# Sheet1.net
KiCad netlist of a schematic drawn in Altium Designer
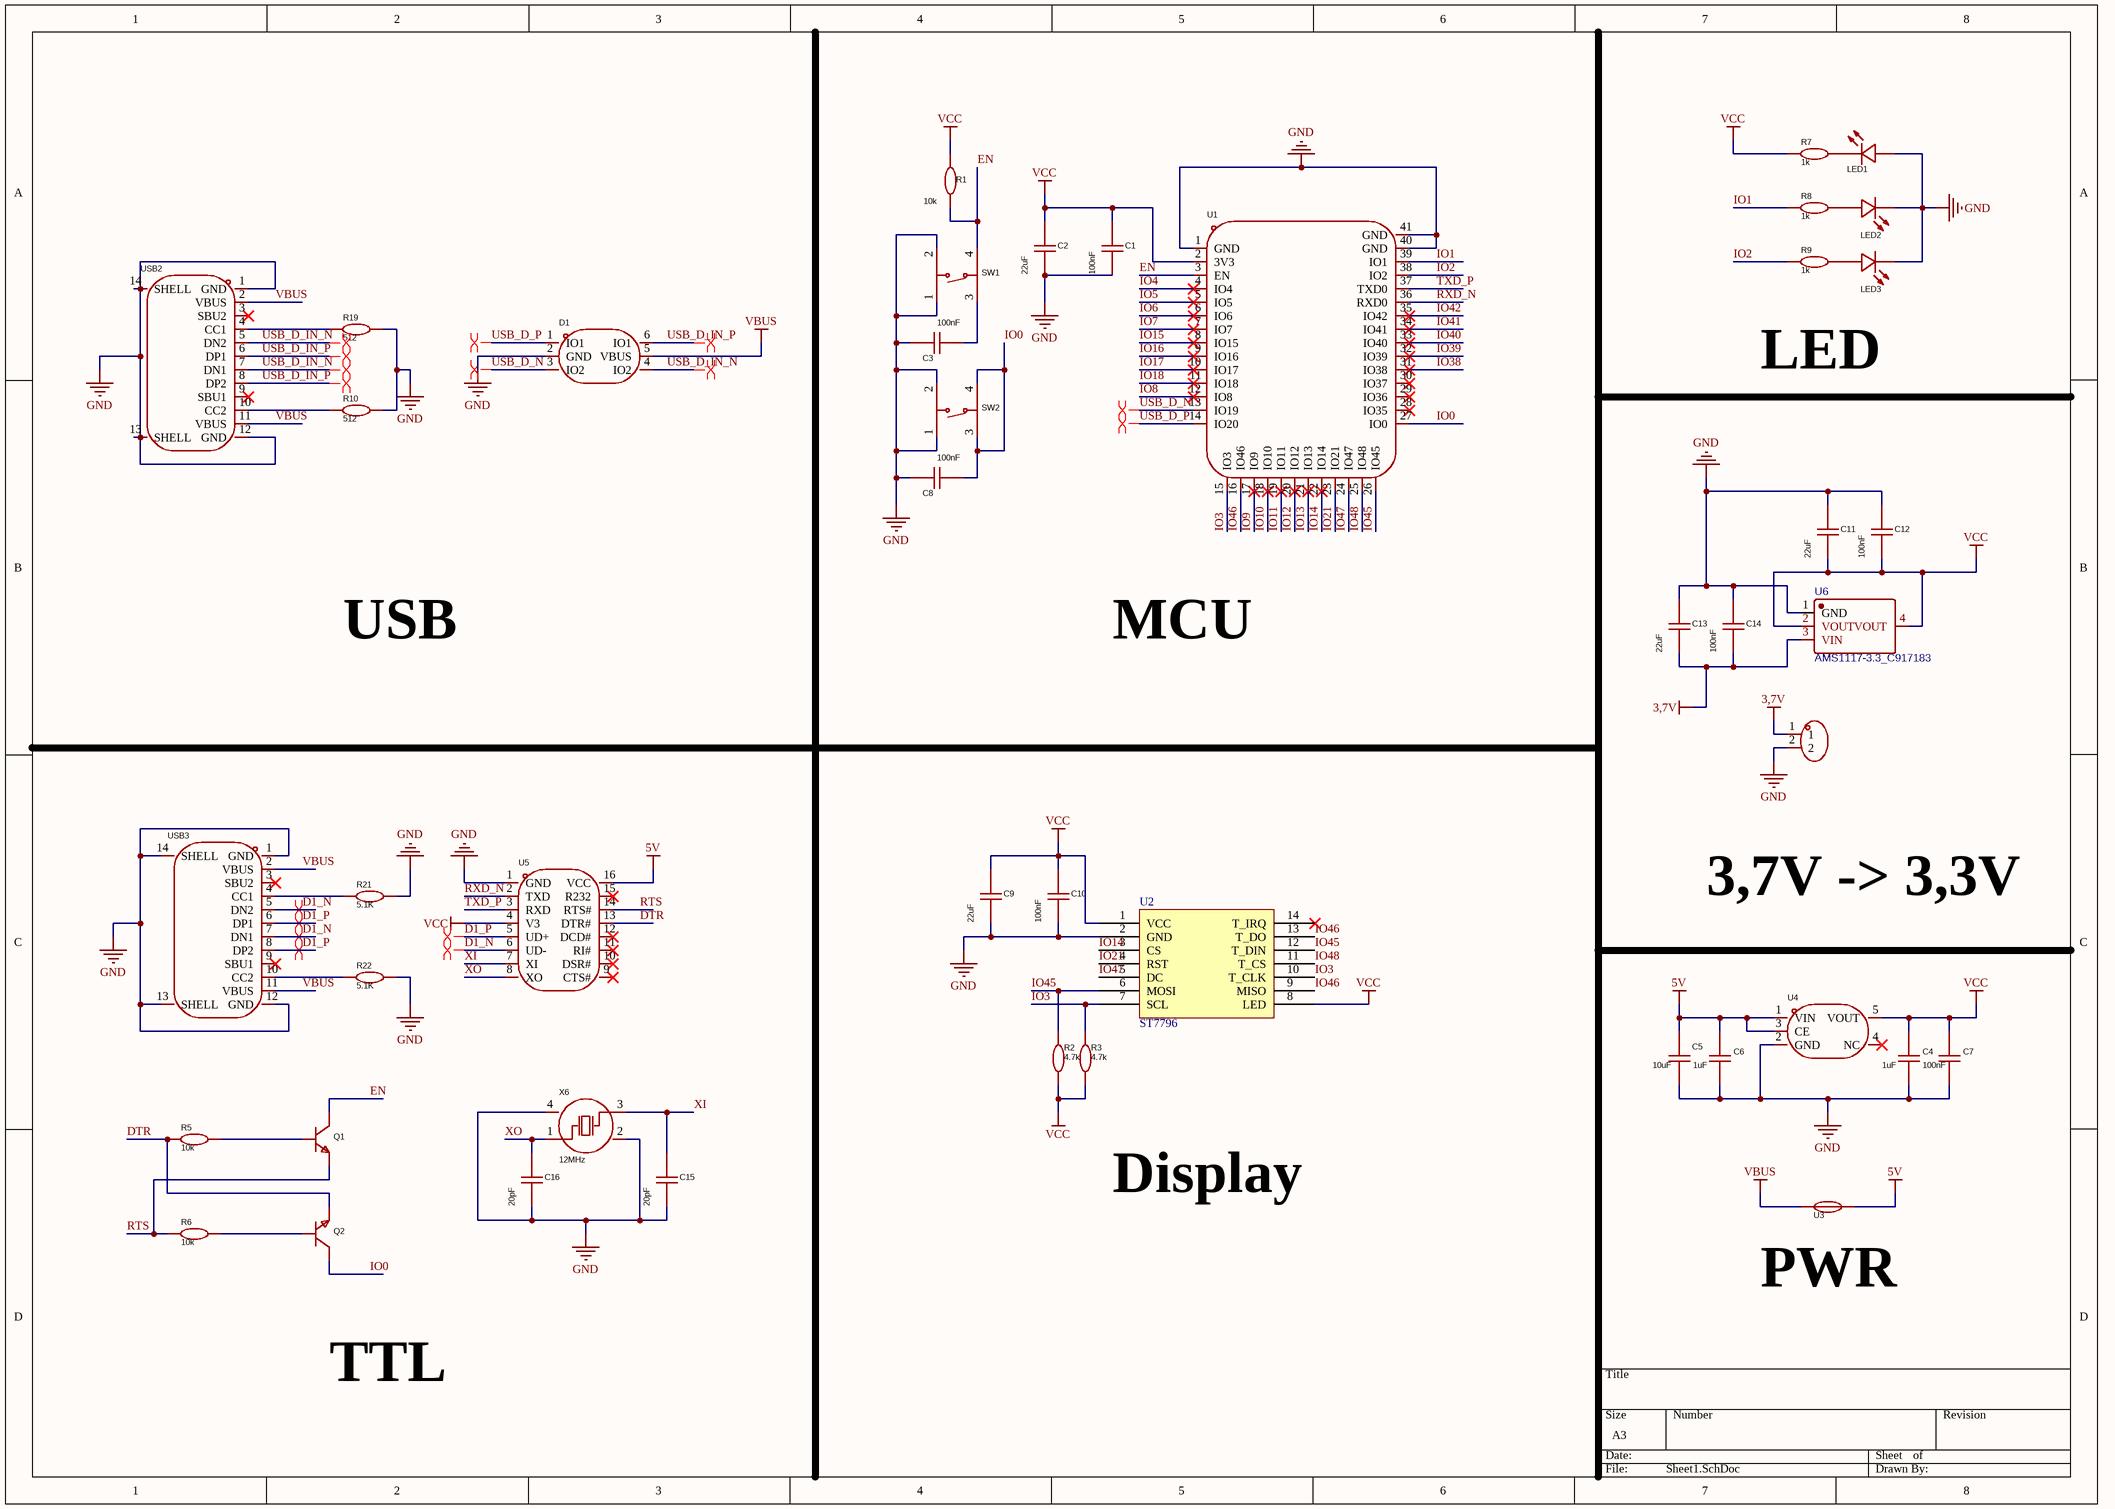
[diagram p0: Sheet1.SchDoc]

(export (version "E")
  (design (tool "Eeschema 10.0.6"))
  (components
    (comp (ref "C1")
      (value "100nF")
      (footprint "C0402")
      (fields
        (field (name "MANUFACTURER") "YAGEO(国巨)")
        (field (name "MANUFACTURER PART") "CC0603KRX7R9BB104")
        (field (name "TOLERANCE") "±10%")
      )
      (libsource (lib "Cap") (part "100n_22u"))
    )
    (comp (ref "C2")
      (value "22uF")
      (footprint "C0402")
      (fields
        (field (name "MANUFACTURER") "YAGEO(国巨)")
        (field (name "MANUFACTURER PART") "CC0603KRX7R9BB104")
        (field (name "TOLERANCE") "±10%")
      )
      (libsource (lib "Cap") (part "100n_22u"))
    )
    (comp (ref "C3")
      (value "100nF")
      (footprint "C0402")
      (fields
        (field (name "MANUFACTURER") "YAGEO(国巨)")
        (field (name "MANUFACTURER PART") "CC0603KRX7R9BB104")
        (field (name "TOLERANCE") "±10%")
      )
      (libsource (lib "Cap") (part "100n_22u"))
    )
    (comp (ref "C4")
      (value "1uF")
      (footprint "C0402")
      (fields
        (field (name "MANUFACTURER") "YAGEO(国巨)")
        (field (name "MANUFACTURER PART") "CC0603KRX7R9BB104")
        (field (name "TOLERANCE") "±10%")
      )
      (libsource (lib "Cap") (part "100n_22u"))
    )
    (comp (ref "C5")
      (value "10uF")
      (footprint "C0402")
      (fields
        (field (name "MANUFACTURER") "YAGEO(国巨)")
        (field (name "MANUFACTURER PART") "CC0603KRX7R9BB104")
        (field (name "TOLERANCE") "±10%")
      )
      (libsource (lib "Cap") (part "100n_22u"))
    )
    (comp (ref "C6")
      (value "1uF")
      (footprint "C0402")
      (fields
        (field (name "MANUFACTURER") "YAGEO(国巨)")
        (field (name "MANUFACTURER PART") "CC0603KRX7R9BB104")
        (field (name "TOLERANCE") "±10%")
      )
      (libsource (lib "Cap") (part "100n_22u"))
    )
    (comp (ref "C7")
      (value "100nF")
      (footprint "C0402")
      (fields
        (field (name "MANUFACTURER") "YAGEO(国巨)")
        (field (name "MANUFACTURER PART") "CC0603KRX7R9BB104")
        (field (name "TOLERANCE") "±10%")
      )
      (libsource (lib "Cap") (part "100n_22u"))
    )
    (comp (ref "C8")
      (value "100nF")
      (footprint "C0402")
      (fields
        (field (name "MANUFACTURER") "YAGEO(国巨)")
        (field (name "MANUFACTURER PART") "CC0603KRX7R9BB104")
        (field (name "TOLERANCE") "±10%")
      )
      (libsource (lib "Cap") (part "100n_22u"))
    )
    (comp (ref "C9")
      (value "22uF")
      (footprint "C0402")
      (fields
        (field (name "MANUFACTURER") "YAGEO(国巨)")
        (field (name "MANUFACTURER PART") "CC0603KRX7R9BB104")
        (field (name "TOLERANCE") "±10%")
      )
      (libsource (lib "Cap") (part "100n_22u"))
    )
    (comp (ref "C10")
      (value "100nF")
      (footprint "C0402")
      (fields
        (field (name "MANUFACTURER") "YAGEO(国巨)")
        (field (name "MANUFACTURER PART") "CC0603KRX7R9BB104")
        (field (name "TOLERANCE") "±10%")
      )
      (libsource (lib "Cap") (part "100n_22u"))
    )
    (comp (ref "C11")
      (value "22uF")
      (footprint "C0402")
      (fields
        (field (name "MANUFACTURER") "YAGEO(国巨)")
        (field (name "MANUFACTURER PART") "CC0603KRX7R9BB104")
        (field (name "TOLERANCE") "±10%")
      )
      (libsource (lib "Cap") (part "100n_22u"))
    )
    (comp (ref "C12")
      (value "100nF")
      (footprint "C0402")
      (fields
        (field (name "MANUFACTURER") "YAGEO(国巨)")
        (field (name "MANUFACTURER PART") "CC0603KRX7R9BB104")
        (field (name "TOLERANCE") "±10%")
      )
      (libsource (lib "Cap") (part "100n_22u"))
    )
    (comp (ref "C13")
      (value "22uF")
      (footprint "C0402")
      (fields
        (field (name "MANUFACTURER") "YAGEO(国巨)")
        (field (name "MANUFACTURER PART") "CC0603KRX7R9BB104")
        (field (name "TOLERANCE") "±10%")
      )
      (libsource (lib "Cap") (part "100n_22u"))
    )
    (comp (ref "C14")
      (value "100nF")
      (footprint "C0402")
      (fields
        (field (name "MANUFACTURER") "YAGEO(国巨)")
        (field (name "MANUFACTURER PART") "CC0603KRX7R9BB104")
        (field (name "TOLERANCE") "±10%")
      )
      (libsource (lib "Cap") (part "100n_22u"))
    )
    (comp (ref "C15")
      (value "20pF")
      (footprint "C0402")
      (fields
        (field (name "MANUFACTURER") "YAGEO(国巨)")
        (field (name "MANUFACTURER PART") "CC0603KRX7R9BB104")
        (field (name "TOLERANCE") "±10%")
      )
      (libsource (lib "Cap") (part "100n_22u"))
    )
    (comp (ref "C16")
      (value "20pF")
      (footprint "C0402")
      (fields
        (field (name "MANUFACTURER") "YAGEO(国巨)")
        (field (name "MANUFACTURER PART") "CC0603KRX7R9BB104")
        (field (name "TOLERANCE") "±10%")
      )
      (libsource (lib "Cap") (part "100n_22u"))
    )
    (comp (ref "D1")
      (value "USBLC6-2SC6")
      (footprint "SOT-23-6_L2.9-W1.6-P0.95-LS2.8-BL")
      (fields (field (name "MANUFACTURER") "TECH PUBLIC(台舟)"))
      (libsource (lib "USBLC6-2SC6_C28276541_") (part "USBLC6-2SC6_C2827654"))
    )
    (comp (ref "LED1")
      (value "MHT192WDT-CYAN")
      (footprint "LED0603-Yel")
      (fields (field (name "MANUFACTURER") "MEIHUA(美华)"))
      (libsource (lib "Led") (part "LED"))
    )
    (comp (ref "LED2")
      (value "MHT192WDT-CYAN")
      (footprint "LED0603-R-RD_BLUE")
      (fields (field (name "MANUFACTURER") "MEIHUA(美华)"))
      (libsource (lib "Led") (part "LED"))
    )
    (comp (ref "LED3")
      (value "MHT192WDT-CYAN")
      (footprint "LED0603-R-RD_BLUE")
      (fields (field (name "MANUFACTURER") "MEIHUA(美华)"))
      (libsource (lib "Led") (part "LED"))
    )
    (comp (ref "Q1")
      (value "S8050")
      (footprint "SOT-23-3_L2.9-W1.3-P1.90-LS2.4-BR")
      (fields (field (name "MANUFACTURER") "YONGYUTAI(永裕泰)"))
      (libsource (lib "S8050_C28918041") (part "S8050_C2891804"))
    )
    (comp (ref "Q2")
      (value "S8050")
      (footprint "SOT-23-3_L2.9-W1.3-P1.90-LS2.4-BR")
      (fields (field (name "MANUFACTURER") "YONGYUTAI(永裕泰)"))
      (libsource (lib "S8050_C28918041") (part "S8050_C2891804"))
    )
    (comp (ref "R1")
      (value "10k")
      (footprint "R0402")
      (fields
        (field (name "MANUFACTURER") "YAGEO(国巨)")
        (field (name "MANUFACTURER PART") "RC0402FR-0710KL")
        (field (name "TOLERANCE") "±1%")
      )
      (libsource (lib "Res") (part "10k"))
    )
    (comp (ref "R2")
      (value "4.7k")
      (footprint "R0402")
      (fields
        (field (name "MANUFACTURER") "YAGEO(国巨)")
        (field (name "MANUFACTURER PART") "RC0402FR-0710KL")
        (field (name "TOLERANCE") "±1%")
      )
      (libsource (lib "Res") (part "10k"))
    )
    (comp (ref "R3")
      (value "4.7k")
      (footprint "R0402")
      (fields
        (field (name "MANUFACTURER") "YAGEO(国巨)")
        (field (name "MANUFACTURER PART") "RC0402FR-0710KL")
        (field (name "TOLERANCE") "±1%")
      )
      (libsource (lib "Res") (part "10k"))
    )
    (comp (ref "R5")
      (value "10k")
      (footprint "R0402")
      (fields
        (field (name "MANUFACTURER") "YAGEO(国巨)")
        (field (name "MANUFACTURER PART") "RC0402FR-0710KL")
        (field (name "TOLERANCE") "±1%")
      )
      (libsource (lib "Res") (part "10k"))
    )
    (comp (ref "R6")
      (value "10k")
      (footprint "R0402")
      (fields
        (field (name "MANUFACTURER") "YAGEO(国巨)")
        (field (name "MANUFACTURER PART") "RC0402FR-0710KL")
        (field (name "TOLERANCE") "±1%")
      )
      (libsource (lib "Res") (part "10k"))
    )
    (comp (ref "R7")
      (value "1k")
      (footprint "R0402")
      (fields
        (field (name "MANUFACTURER") "YAGEO(国巨)")
        (field (name "MANUFACTURER PART") "RC0402FR-0710KL")
        (field (name "TOLERANCE") "±1%")
      )
      (libsource (lib "Res") (part "10k"))
    )
    (comp (ref "R8")
      (value "1k")
      (footprint "R0402")
      (fields
        (field (name "MANUFACTURER") "YAGEO(国巨)")
        (field (name "MANUFACTURER PART") "RC0402FR-0710KL")
        (field (name "TOLERANCE") "±1%")
      )
      (libsource (lib "Res") (part "10k"))
    )
    (comp (ref "R9")
      (value "1k")
      (footprint "R0402")
      (fields
        (field (name "MANUFACTURER") "YAGEO(国巨)")
        (field (name "MANUFACTURER PART") "RC0402FR-0710KL")
        (field (name "TOLERANCE") "±1%")
      )
      (libsource (lib "Res") (part "10k"))
    )
    (comp (ref "R10")
      (value "512")
      (footprint "R0402")
      (fields
        (field (name "MANUFACTURER") "YAGEO(国巨)")
        (field (name "MANUFACTURER PART") "RC0402FR-0710KL")
        (field (name "TOLERANCE") "±1%")
      )
      (libsource (lib "Res") (part "10k"))
    )
    (comp (ref "R19")
      (value "512")
      (footprint "R0402")
      (fields
        (field (name "MANUFACTURER") "YAGEO(国巨)")
        (field (name "MANUFACTURER PART") "RC0402FR-0710KL")
        (field (name "TOLERANCE") "±1%")
      )
      (libsource (lib "Res") (part "10k"))
    )
    (comp (ref "R21")
      (value "5.1K")
      (footprint "R0402")
      (fields
        (field (name "MANUFACTURER") "YAGEO(国巨)")
        (field (name "MANUFACTURER PART") "RC0402FR-0710KL")
        (field (name "TOLERANCE") "±1%")
      )
      (libsource (lib "Res") (part "10k"))
    )
    (comp (ref "R22")
      (value "5.1K")
      (footprint "R0402")
      (fields
        (field (name "MANUFACTURER") "YAGEO(国巨)")
        (field (name "MANUFACTURER PART") "RC0402FR-0710KL")
        (field (name "TOLERANCE") "±1%")
      )
      (libsource (lib "Res") (part "10k"))
    )
    (comp (ref "SW1")
      (value "TS-1089S-02526")
      (footprint "SW-SMD_4P-L4.2-W3.3-P2.15-LS5.1")
      (fields (field (name "MANUFACTURER") "XUNPU(讯普)"))
      (libsource (lib "TS-1089S-025261_TS-1089S-02526") (part "TS-1089S-02526"))
    )
    (comp (ref "SW2")
      (value "TS-1089S-02526")
      (footprint "SW-SMD_4P-L4.2-W3.3-P2.15-LS5.1")
      (fields (field (name "MANUFACTURER") "XUNPU(讯普)"))
      (libsource (lib "TS-1089S-025261_TS-1089S-02526") (part "TS-1089S-02526"))
    )
    (comp (ref "U1")
      (value "ESP32-S3-WROOM-1-N16R2")
      (footprint "WIRELM-SMD_ESP32-S3-WROOM-1")
      (fields (field (name "MANUFACTURER") "ESPRESSIF(乐鑫)"))
      (libsource (lib "ESP32-S3-WROOM-1(N16R2)") (part "ESP32-S3-WROOM-1-N16R2"))
    )
    (comp (ref "U2") (value "ST7796") (footprint "ST7796") (libsource (lib "Schlib1") (part "ST7796")))
    (comp (ref "U3")
      (value "SMD0805B050TF")
      (footprint "F0805")
      (fields (field (name "MANUFACTURER") "Brightking(君耀电子)"))
      (libsource (lib "SMD0805B050TF") (part "SMD0805B050TF"))
    )
    (comp (ref "U4")
      (value "RT9013-33GB-JSM")
      (footprint "SOT-23-5_L2.9-W1.6-P0.95-LS2.8-BR")
      (fields (field (name "MANUFACTURER") "JSMSEMI(杰盛微)"))
      (libsource (lib "RT9013-33GB") (part "RT9013-33GB-JSM"))
    )
    (comp (ref "U5")
      (value "CH340G")
      (footprint "SOIC-16_L9.9-W3.9-P1.27-LS6.0-BL")
      (fields (field (name "MANUFACTURER") "WCH(南京沁恒)"))
      (libsource (lib "CH340G") (part "CH340G"))
    )
    (comp (ref "U6")
      (value "AMS1117-3.3_C917183")
      (footprint "SOT-223-3_L6.7-W3.7-P2.30-LS7.0-BR")
      (fields
        (field (name "MANUFACTURER") "JSMSEMI(杰盛微)")
        (field (name "MANUFACTURER PART") "AMS1117-3.3")
        (field (name "CONTRIBUTOR") "LCSC")
      )
      (libsource (lib "AMS1117-3.3") (part "AMS1117-3.3_C917183"))
    )
    (comp (ref "U7")
      (value "WAFER-XH254Z-2A")
      (footprint "CONN-TH_2P-P2.50_XH-2A_3045048")
      (fields (field (name "MANUFACTURER") "HANBO(汉博)"))
      (libsource (lib "WAFER-XH254Z-2A") (part "WAFER-XH254Z-2A"))
    )
    (comp (ref "USB2")
      (value "TYPE-C 16PIN 2MD(073)")
      (footprint "USB-C-SMD_TYPE-C-6PIN-2MD-073")
      (fields (field (name "MANUFACTURER") "SHOU HAN(首韩)"))
      (libsource (lib "TYPE-C 16PIN 2MD(073)") (part "TYPE-C 16PIN 2MD(073)"))
    )
    (comp (ref "USB3")
      (value "TYPE-C 16PIN 2MD(073)")
      (footprint "USB-C-SMD_TYPE-C-6PIN-2MD-073")
      (fields (field (name "MANUFACTURER") "SHOU HAN(首韩)"))
      (libsource (lib "TYPE-C 16PIN 2MD(073)") (part "TYPE-C 16PIN 2MD(073)"))
    )
    (comp (ref "X6")
      (value "12MHz")
      (footprint "CRYSTAL-SMD_4P-L3.2-W2.5-BL")
      (fields (field (name "MANUFACTURER") "YXC(扬兴晶振)") (field (name "MANUFACTURER PART") "X322512MSB4SI"))
      (libsource (lib "X322512MSB4SI") (part "X322512MSB4SI"))
    )
  )
  (nets
    (net (code "1") (name "/D1_N") (class "Default")
      (node (ref "U5") (pin "6") (pinfunction "UD-_6") (pintype "passive"))
      (node (ref "USB3") (pin "5") (pinfunction "DN2_5") (pintype "passive"))
      (node (ref "USB3") (pin "7") (pinfunction "DN1_7") (pintype "passive"))
    )
    (net (code "2") (name "/D1_P") (class "Default")
      (node (ref "U5") (pin "5") (pinfunction "UD+_5") (pintype "passive"))
      (node (ref "USB3") (pin "6") (pinfunction "DP1_6") (pintype "passive"))
      (node (ref "USB3") (pin "8") (pinfunction "DP2_8") (pintype "passive"))
    )
    (net (code "3") (name "/DTR") (class "Default")
      (node (ref "Q2") (pin "2") (pinfunction "E_2") (pintype "passive"))
      (node (ref "R5") (pin "2") (pinfunction "2_2") (pintype "passive"))
      (node (ref "U5") (pin "13") (pinfunction "DTR#_13") (pintype "passive"))
    )
    (net (code "4") (name "/EN") (class "Default")
      (node (ref "Q1") (pin "3") (pinfunction "C_3") (pintype "passive"))
      (node (ref "R1") (pin "1") (pinfunction "1_1") (pintype "passive"))
      (node (ref "SW1") (pin "4") (pinfunction "4_4") (pintype "passive"))
      (node (ref "U1") (pin "3") (pinfunction "EN_3") (pintype "passive"))
    )
    (net (code "5") (name "/IO0") (class "Default")
      (node (ref "C8") (pin "1") (pinfunction "1_1") (pintype "passive"))
      (node (ref "Q2") (pin "3") (pinfunction "C_3") (pintype "passive"))
      (node (ref "SW2") (pin "3") (pinfunction "3_3") (pintype "passive"))
      (node (ref "SW2") (pin "4") (pinfunction "4_4") (pintype "passive"))
      (node (ref "U1") (pin "27") (pinfunction "IO0_27") (pintype "passive"))
    )
    (net (code "6") (name "/IO1") (class "Default")
      (node (ref "R8") (pin "2") (pinfunction "2_2") (pintype "passive"))
      (node (ref "U1") (pin "39") (pinfunction "IO1_39") (pintype "passive"))
    )
    (net (code "7") (name "/IO2") (class "Default")
      (node (ref "R9") (pin "2") (pinfunction "2_2") (pintype "passive"))
      (node (ref "U1") (pin "38") (pinfunction "IO2_38") (pintype "passive"))
    )
    (net (code "8") (name "/IO3") (class "Default")
      (node (ref "R3") (pin "1") (pinfunction "1_1") (pintype "passive"))
      (node (ref "U1") (pin "15") (pinfunction "IO3_15") (pintype "passive"))
      (node (ref "U2") (pin "10") (pinfunction "T_CLK_10") (pintype "passive"))
      (node (ref "U2") (pin "7") (pinfunction "SCL_7") (pintype "passive"))
    )
    (net (code "9") (name "/IO4") (class "Default")
      (node (ref "U1") (pin "4") (pinfunction "IO4_4") (pintype "passive+no_connect"))
    )
    (net (code "10") (name "/IO5") (class "Default")
      (node (ref "U1") (pin "5") (pinfunction "IO5_5") (pintype "passive+no_connect"))
    )
    (net (code "11") (name "/IO6") (class "Default")
      (node (ref "U1") (pin "6") (pinfunction "IO6_6") (pintype "passive+no_connect"))
    )
    (net (code "12") (name "/IO7") (class "Default")
      (node (ref "U1") (pin "7") (pinfunction "IO7_7") (pintype "passive+no_connect"))
    )
    (net (code "13") (name "/IO8") (class "Default")
      (node (ref "U1") (pin "12") (pinfunction "IO8_12") (pintype "passive+no_connect"))
    )
    (net (code "14") (name "/IO9") (class "Default")
      (node (ref "U1") (pin "17") (pinfunction "IO9_17") (pintype "passive+no_connect"))
    )
    (net (code "15") (name "/IO10") (class "Default")
      (node (ref "U1") (pin "18") (pinfunction "IO10_18") (pintype "passive+no_connect"))
    )
    (net (code "16") (name "/IO11") (class "Default")
      (node (ref "U1") (pin "19") (pinfunction "IO11_19") (pintype "passive+no_connect"))
    )
    (net (code "17") (name "/IO12") (class "Default")
      (node (ref "U1") (pin "20") (pinfunction "IO12_20") (pintype "passive+no_connect"))
    )
    (net (code "18") (name "/IO13") (class "Default")
      (node (ref "U1") (pin "21") (pinfunction "IO13_21") (pintype "passive+no_connect"))
    )
    (net (code "19") (name "/IO14") (class "Default")
      (node (ref "U1") (pin "22") (pinfunction "IO14_22") (pintype "passive"))
      (node (ref "U2") (pin "3") (pinfunction "CS_3") (pintype "passive"))
    )
    (net (code "20") (name "/IO15") (class "Default")
      (node (ref "U1") (pin "8") (pinfunction "IO15_8") (pintype "passive+no_connect"))
    )
    (net (code "21") (name "/IO16") (class "Default")
      (node (ref "U1") (pin "9") (pinfunction "IO16_9") (pintype "passive+no_connect"))
    )
    (net (code "22") (name "/IO17") (class "Default")
      (node (ref "U1") (pin "10") (pinfunction "IO17_10") (pintype "passive+no_connect"))
    )
    (net (code "23") (name "/IO18") (class "Default")
      (node (ref "U1") (pin "11") (pinfunction "IO18_11") (pintype "passive+no_connect"))
    )
    (net (code "24") (name "/IO21") (class "Default")
      (node (ref "U1") (pin "23") (pinfunction "IO21_23") (pintype "passive"))
      (node (ref "U2") (pin "4") (pinfunction "RST_4") (pintype "passive"))
    )
    (net (code "25") (name "/IO38") (class "Default")
      (node (ref "U1") (pin "31") (pinfunction "IO38_31") (pintype "passive+no_connect"))
    )
    (net (code "26") (name "/IO39") (class "Default")
      (node (ref "U1") (pin "32") (pinfunction "IO39_32") (pintype "passive+no_connect"))
    )
    (net (code "27") (name "/IO40") (class "Default")
      (node (ref "U1") (pin "33") (pinfunction "IO40_33") (pintype "passive+no_connect"))
    )
    (net (code "28") (name "/IO41") (class "Default")
      (node (ref "U1") (pin "34") (pinfunction "IO41_34") (pintype "passive+no_connect"))
    )
    (net (code "29") (name "/IO42") (class "Default")
      (node (ref "U1") (pin "35") (pinfunction "IO42_35") (pintype "passive+no_connect"))
    )
    (net (code "30") (name "/IO45") (class "Default")
      (node (ref "R2") (pin "1") (pinfunction "1_1") (pintype "passive"))
      (node (ref "U1") (pin "26") (pinfunction "IO45_26") (pintype "passive"))
      (node (ref "U2") (pin "12") (pinfunction "T_DIN_12") (pintype "passive"))
      (node (ref "U2") (pin "6") (pinfunction "MOSI_6") (pintype "passive"))
    )
    (net (code "31") (name "/IO46") (class "Default")
      (node (ref "U1") (pin "16") (pinfunction "IO46_16") (pintype "passive"))
      (node (ref "U2") (pin "13") (pinfunction "T_DO_13") (pintype "passive"))
      (node (ref "U2") (pin "9") (pinfunction "MISO_9") (pintype "passive"))
    )
    (net (code "32") (name "/IO47") (class "Default")
      (node (ref "U1") (pin "24") (pinfunction "IO47_24") (pintype "passive"))
      (node (ref "U2") (pin "5") (pinfunction "DC_5") (pintype "passive"))
    )
    (net (code "33") (name "/IO48") (class "Default")
      (node (ref "U1") (pin "25") (pinfunction "IO48_25") (pintype "passive"))
      (node (ref "U2") (pin "11") (pinfunction "T_CS_11") (pintype "passive"))
    )
    (net (code "34") (name "/RTS") (class "Default")
      (node (ref "Q1") (pin "2") (pinfunction "E_2") (pintype "passive"))
      (node (ref "R6") (pin "2") (pinfunction "2_2") (pintype "passive"))
      (node (ref "U5") (pin "14") (pinfunction "RTS#_14") (pintype "passive"))
    )
    (net (code "35") (name "/RXD_N") (class "Default")
      (node (ref "U1") (pin "36") (pinfunction "RXD0_36") (pintype "passive"))
      (node (ref "U5") (pin "2") (pinfunction "TXD_2") (pintype "passive"))
    )
    (net (code "36") (name "/TXD_P") (class "Default")
      (node (ref "U1") (pin "37") (pinfunction "TXD0_37") (pintype "passive"))
      (node (ref "U5") (pin "3") (pinfunction "RXD_3") (pintype "passive"))
    )
    (net (code "37") (name "/USB_D_IN_N") (class "Default")
      (node (ref "D1") (pin "4") (pinfunction "IO2_4") (pintype "passive"))
      (node (ref "USB2") (pin "5") (pinfunction "DN2_5") (pintype "passive"))
      (node (ref "USB2") (pin "7") (pinfunction "DN1_7") (pintype "passive"))
    )
    (net (code "38") (name "/USB_D_IN_P") (class "Default")
      (node (ref "D1") (pin "6") (pinfunction "IO1_6") (pintype "passive"))
      (node (ref "USB2") (pin "6") (pinfunction "DP1_6") (pintype "passive"))
      (node (ref "USB2") (pin "8") (pinfunction "DP2_8") (pintype "passive"))
    )
    (net (code "39") (name "/USB_D_N") (class "Default")
      (node (ref "D1") (pin "3") (pinfunction "IO2_3") (pintype "passive"))
      (node (ref "U1") (pin "13") (pinfunction "IO19_13") (pintype "passive"))
    )
    (net (code "40") (name "/USB_D_P") (class "Default")
      (node (ref "D1") (pin "1") (pinfunction "IO1_1") (pintype "passive"))
      (node (ref "U1") (pin "14") (pinfunction "IO20_14") (pintype "passive"))
    )
    (net (code "41") (name "/XI") (class "Default")
      (node (ref "C15") (pin "2") (pinfunction "2_2") (pintype "passive"))
      (node (ref "U5") (pin "7") (pinfunction "XI_7") (pintype "passive"))
      (node (ref "X6") (pin "3") (pinfunction "OSC2_3") (pintype "passive"))
    )
    (net (code "42") (name "/XO") (class "Default")
      (node (ref "C16") (pin "2") (pinfunction "2_2") (pintype "passive"))
      (node (ref "U5") (pin "8") (pinfunction "XO_8") (pintype "passive"))
      (node (ref "X6") (pin "1") (pinfunction "OSC1_1") (pintype "passive"))
    )
    (net (code "43") (name "3,7V") (class "Default")
      (node (ref "C13") (pin "1") (pinfunction "1_1") (pintype "passive"))
      (node (ref "C14") (pin "1") (pinfunction "1_1") (pintype "passive"))
      (node (ref "U6") (pin "3") (pinfunction "VIN_3") (pintype "passive"))
      (node (ref "U7") (pin "1") (pinfunction "1_1") (pintype "passive"))
    )
    (net (code "44") (name "5V") (class "Default")
      (node (ref "C5") (pin "1") (pinfunction "1_1") (pintype "passive"))
      (node (ref "C6") (pin "2") (pinfunction "2_2") (pintype "passive"))
      (node (ref "U3") (pin "2") (pinfunction "2_2") (pintype "passive"))
      (node (ref "U4") (pin "1") (pinfunction "VIN_1") (pintype "passive"))
      (node (ref "U4") (pin "3") (pinfunction "CE_3") (pintype "passive"))
      (node (ref "U5") (pin "16") (pinfunction "VCC_16") (pintype "passive"))
    )
    (net (code "45") (name "GND") (class "Default")
      (node (ref "C1") (pin "1") (pinfunction "1_1") (pintype "passive"))
      (node (ref "C10") (pin "1") (pinfunction "1_1") (pintype "passive"))
      (node (ref "C11") (pin "2") (pinfunction "2_2") (pintype "passive"))
      (node (ref "C12") (pin "2") (pinfunction "2_2") (pintype "passive"))
      (node (ref "C13") (pin "2") (pinfunction "2_2") (pintype "passive"))
      (node (ref "C14") (pin "2") (pinfunction "2_2") (pintype "passive"))
      (node (ref "C15") (pin "1") (pinfunction "1_1") (pintype "passive"))
      (node (ref "C16") (pin "1") (pinfunction "1_1") (pintype "passive"))
      (node (ref "C2") (pin "1") (pinfunction "1_1") (pintype "passive"))
      (node (ref "C3") (pin "2") (pinfunction "2_2") (pintype "passive"))
      (node (ref "C4") (pin "1") (pinfunction "1_1") (pintype "passive"))
      (node (ref "C5") (pin "2") (pinfunction "2_2") (pintype "passive"))
      (node (ref "C6") (pin "1") (pinfunction "1_1") (pintype "passive"))
      (node (ref "C7") (pin "1") (pinfunction "1_1") (pintype "passive"))
      (node (ref "C8") (pin "2") (pinfunction "2_2") (pintype "passive"))
      (node (ref "C9") (pin "1") (pinfunction "1_1") (pintype "passive"))
      (node (ref "D1") (pin "2") (pinfunction "GND_2") (pintype "passive"))
      (node (ref "LED1") (pin "2") (pinfunction "K_2") (pintype "passive"))
      (node (ref "LED2") (pin "1") (pinfunction "A_1") (pintype "passive"))
      (node (ref "LED3") (pin "1") (pinfunction "A_1") (pintype "passive"))
      (node (ref "R10") (pin "1") (pinfunction "1_1") (pintype "passive"))
      (node (ref "R19") (pin "1") (pinfunction "1_1") (pintype "passive"))
      (node (ref "R21") (pin "1") (pinfunction "1_1") (pintype "passive"))
      (node (ref "R22") (pin "1") (pinfunction "1_1") (pintype "passive"))
      (node (ref "SW1") (pin "1") (pinfunction "1_1") (pintype "passive"))
      (node (ref "SW1") (pin "2") (pinfunction "2_2") (pintype "passive"))
      (node (ref "SW2") (pin "1") (pinfunction "1_1") (pintype "passive"))
      (node (ref "SW2") (pin "2") (pinfunction "2_2") (pintype "passive"))
      (node (ref "U1") (pin "1") (pinfunction "GND_1") (pintype "passive"))
      (node (ref "U1") (pin "40") (pinfunction "GND_40") (pintype "passive"))
      (node (ref "U1") (pin "41") (pinfunction "GND_41") (pintype "passive"))
      (node (ref "U2") (pin "2") (pinfunction "GND_2") (pintype "passive"))
      (node (ref "U4") (pin "2") (pinfunction "GND_2") (pintype "passive"))
      (node (ref "U5") (pin "1") (pinfunction "GND_1") (pintype "passive"))
      (node (ref "U6") (pin "1") (pinfunction "GND_1") (pintype "passive"))
      (node (ref "U7") (pin "2") (pinfunction "2_2") (pintype "passive"))
      (node (ref "USB2") (pin "1") (pinfunction "GND_1") (pintype "passive"))
      (node (ref "USB2") (pin "12") (pinfunction "GND_12") (pintype "passive"))
      (node (ref "USB2") (pin "13") (pinfunction "SHELL_13") (pintype "passive"))
      (node (ref "USB2") (pin "14") (pinfunction "SHELL_14") (pintype "passive"))
      (node (ref "USB3") (pin "1") (pinfunction "GND_1") (pintype "passive"))
      (node (ref "USB3") (pin "12") (pinfunction "GND_12") (pintype "passive"))
      (node (ref "USB3") (pin "13") (pinfunction "SHELL_13") (pintype "passive"))
      (node (ref "USB3") (pin "14") (pinfunction "SHELL_14") (pintype "passive"))
      (node (ref "X6") (pin "2") (pinfunction "GND_2") (pintype "passive"))
      (node (ref "X6") (pin "4") (pinfunction "GND_4") (pintype "passive"))
    )
    (net (code "46") (name "Net-(C3-Pad1)") (class "Default")
      (node (ref "C3") (pin "1") (pinfunction "1_1") (pintype "passive"))
      (node (ref "SW1") (pin "3") (pinfunction "3_3") (pintype "passive"))
    )
    (net (code "47") (name "Net-(LED1-A)") (class "Default")
      (node (ref "LED1") (pin "1") (pinfunction "A_1") (pintype "passive"))
      (node (ref "R7") (pin "1") (pinfunction "1_1") (pintype "passive"))
    )
    (net (code "48") (name "Net-(LED2-K)") (class "Default")
      (node (ref "LED2") (pin "2") (pinfunction "K_2") (pintype "passive"))
      (node (ref "R8") (pin "1") (pinfunction "1_1") (pintype "passive"))
    )
    (net (code "49") (name "Net-(LED3-K)") (class "Default")
      (node (ref "LED3") (pin "2") (pinfunction "K_2") (pintype "passive"))
      (node (ref "R9") (pin "1") (pinfunction "1_1") (pintype "passive"))
    )
    (net (code "50") (name "Net-(Q1-B)") (class "Default")
      (node (ref "Q1") (pin "1") (pinfunction "B_1") (pintype "passive"))
      (node (ref "R5") (pin "1") (pinfunction "1_1") (pintype "passive"))
    )
    (net (code "51") (name "Net-(Q2-B)") (class "Default")
      (node (ref "Q2") (pin "1") (pinfunction "B_1") (pintype "passive"))
      (node (ref "R6") (pin "1") (pinfunction "1_1") (pintype "passive"))
    )
    (net (code "52") (name "Net-(USB2-CC1)") (class "Default")
      (node (ref "R19") (pin "2") (pinfunction "2_2") (pintype "passive"))
      (node (ref "USB2") (pin "4") (pinfunction "CC1_4") (pintype "passive"))
    )
    (net (code "53") (name "Net-(USB2-CC2)") (class "Default")
      (node (ref "R10") (pin "2") (pinfunction "2_2") (pintype "passive"))
      (node (ref "USB2") (pin "10") (pinfunction "CC2_10") (pintype "passive"))
    )
    (net (code "54") (name "Net-(USB3-CC1)") (class "Default")
      (node (ref "R21") (pin "2") (pinfunction "2_2") (pintype "passive"))
      (node (ref "USB3") (pin "4") (pinfunction "CC1_4") (pintype "passive"))
    )
    (net (code "55") (name "Net-(USB3-CC2)") (class "Default")
      (node (ref "R22") (pin "2") (pinfunction "2_2") (pintype "passive"))
      (node (ref "USB3") (pin "10") (pinfunction "CC2_10") (pintype "passive"))
    )
    (net (code "56") (name "VBUS") (class "Default")
      (node (ref "D1") (pin "5") (pinfunction "VBUS_5") (pintype "passive"))
      (node (ref "U3") (pin "1") (pinfunction "1_1") (pintype "passive"))
      (node (ref "USB2") (pin "11") (pinfunction "VBUS_11") (pintype "passive"))
      (node (ref "USB2") (pin "2") (pinfunction "VBUS_2") (pintype "passive"))
      (node (ref "USB3") (pin "11") (pinfunction "VBUS_11") (pintype "passive"))
      (node (ref "USB3") (pin "2") (pinfunction "VBUS_2") (pintype "passive"))
    )
    (net (code "57") (name "VCC") (class "Default")
      (node (ref "C1") (pin "2") (pinfunction "2_2") (pintype "passive"))
      (node (ref "C10") (pin "2") (pinfunction "2_2") (pintype "passive"))
      (node (ref "C11") (pin "1") (pinfunction "1_1") (pintype "passive"))
      (node (ref "C12") (pin "1") (pinfunction "1_1") (pintype "passive"))
      (node (ref "C2") (pin "2") (pinfunction "2_2") (pintype "passive"))
      (node (ref "C4") (pin "2") (pinfunction "2_2") (pintype "passive"))
      (node (ref "C7") (pin "2") (pinfunction "2_2") (pintype "passive"))
      (node (ref "C9") (pin "2") (pinfunction "2_2") (pintype "passive"))
      (node (ref "R1") (pin "2") (pinfunction "2_2") (pintype "passive"))
      (node (ref "R2") (pin "2") (pinfunction "2_2") (pintype "passive"))
      (node (ref "R3") (pin "2") (pinfunction "2_2") (pintype "passive"))
      (node (ref "R7") (pin "2") (pinfunction "2_2") (pintype "passive"))
      (node (ref "U1") (pin "2") (pinfunction "3V3_2") (pintype "passive"))
      (node (ref "U2") (pin "1") (pinfunction "VCC_1") (pintype "passive"))
      (node (ref "U2") (pin "8") (pinfunction "LED_8") (pintype "passive"))
      (node (ref "U4") (pin "5") (pinfunction "VOUT_5") (pintype "passive"))
      (node (ref "U5") (pin "4") (pinfunction "V3_4") (pintype "passive"))
      (node (ref "U6") (pin "2") (pinfunction "VOUT_2") (pintype "passive"))
      (node (ref "U6") (pin "4") (pinfunction "VOUT_4") (pintype "passive"))
    )
    (net (code "58") (name "unconnected-(U1-IO35-Pad28)") (class "Default")
      (node (ref "U1") (pin "28") (pinfunction "IO35_28") (pintype "passive+no_connect"))
    )
    (net (code "59") (name "unconnected-(U1-IO36-Pad29)") (class "Default")
      (node (ref "U1") (pin "29") (pinfunction "IO36_29") (pintype "passive+no_connect"))
    )
    (net (code "60") (name "unconnected-(U1-IO37-Pad30)") (class "Default")
      (node (ref "U1") (pin "30") (pinfunction "IO37_30") (pintype "passive+no_connect"))
    )
    (net (code "61") (name "unconnected-(U2-T_IRQ-Pad14)") (class "Default")
      (node (ref "U2") (pin "14") (pinfunction "T_IRQ_14") (pintype "passive+no_connect"))
    )
    (net (code "62") (name "unconnected-(U4-NC-Pad4)") (class "Default")
      (node (ref "U4") (pin "4") (pinfunction "NC_4") (pintype "passive+no_connect"))
    )
    (net (code "63") (name "unconnected-(U5-CTS#-Pad9)") (class "Default")
      (node (ref "U5") (pin "9") (pinfunction "CTS#_9") (pintype "passive+no_connect"))
    )
    (net (code "64") (name "unconnected-(U5-DCD#-Pad12)") (class "Default")
      (node (ref "U5") (pin "12") (pinfunction "DCD#_12") (pintype "passive+no_connect"))
    )
    (net (code "65") (name "unconnected-(U5-DSR#-Pad10)") (class "Default")
      (node (ref "U5") (pin "10") (pinfunction "DSR#_10") (pintype "passive+no_connect"))
    )
    (net (code "66") (name "unconnected-(U5-R232-Pad15)") (class "Default")
      (node (ref "U5") (pin "15") (pinfunction "R232_15") (pintype "passive+no_connect"))
    )
    (net (code "67") (name "unconnected-(U5-RI#-Pad11)") (class "Default")
      (node (ref "U5") (pin "11") (pinfunction "RI#_11") (pintype "passive+no_connect"))
    )
    (net (code "68") (name "unconnected-(USB2-SBU1-Pad9)") (class "Default")
      (node (ref "USB2") (pin "9") (pinfunction "SBU1_9") (pintype "passive+no_connect"))
    )
    (net (code "69") (name "unconnected-(USB2-SBU2-Pad3)") (class "Default")
      (node (ref "USB2") (pin "3") (pinfunction "SBU2_3") (pintype "passive+no_connect"))
    )
    (net (code "70") (name "unconnected-(USB3-SBU1-Pad9)") (class "Default")
      (node (ref "USB3") (pin "9") (pinfunction "SBU1_9") (pintype "passive+no_connect"))
    )
    (net (code "71") (name "unconnected-(USB3-SBU2-Pad3)") (class "Default")
      (node (ref "USB3") (pin "3") (pinfunction "SBU2_3") (pintype "passive+no_connect"))
    )
  )
)
